# LINEARDriver_Driver.net
KiCad netlist of a schematic drawn in Altium Designer
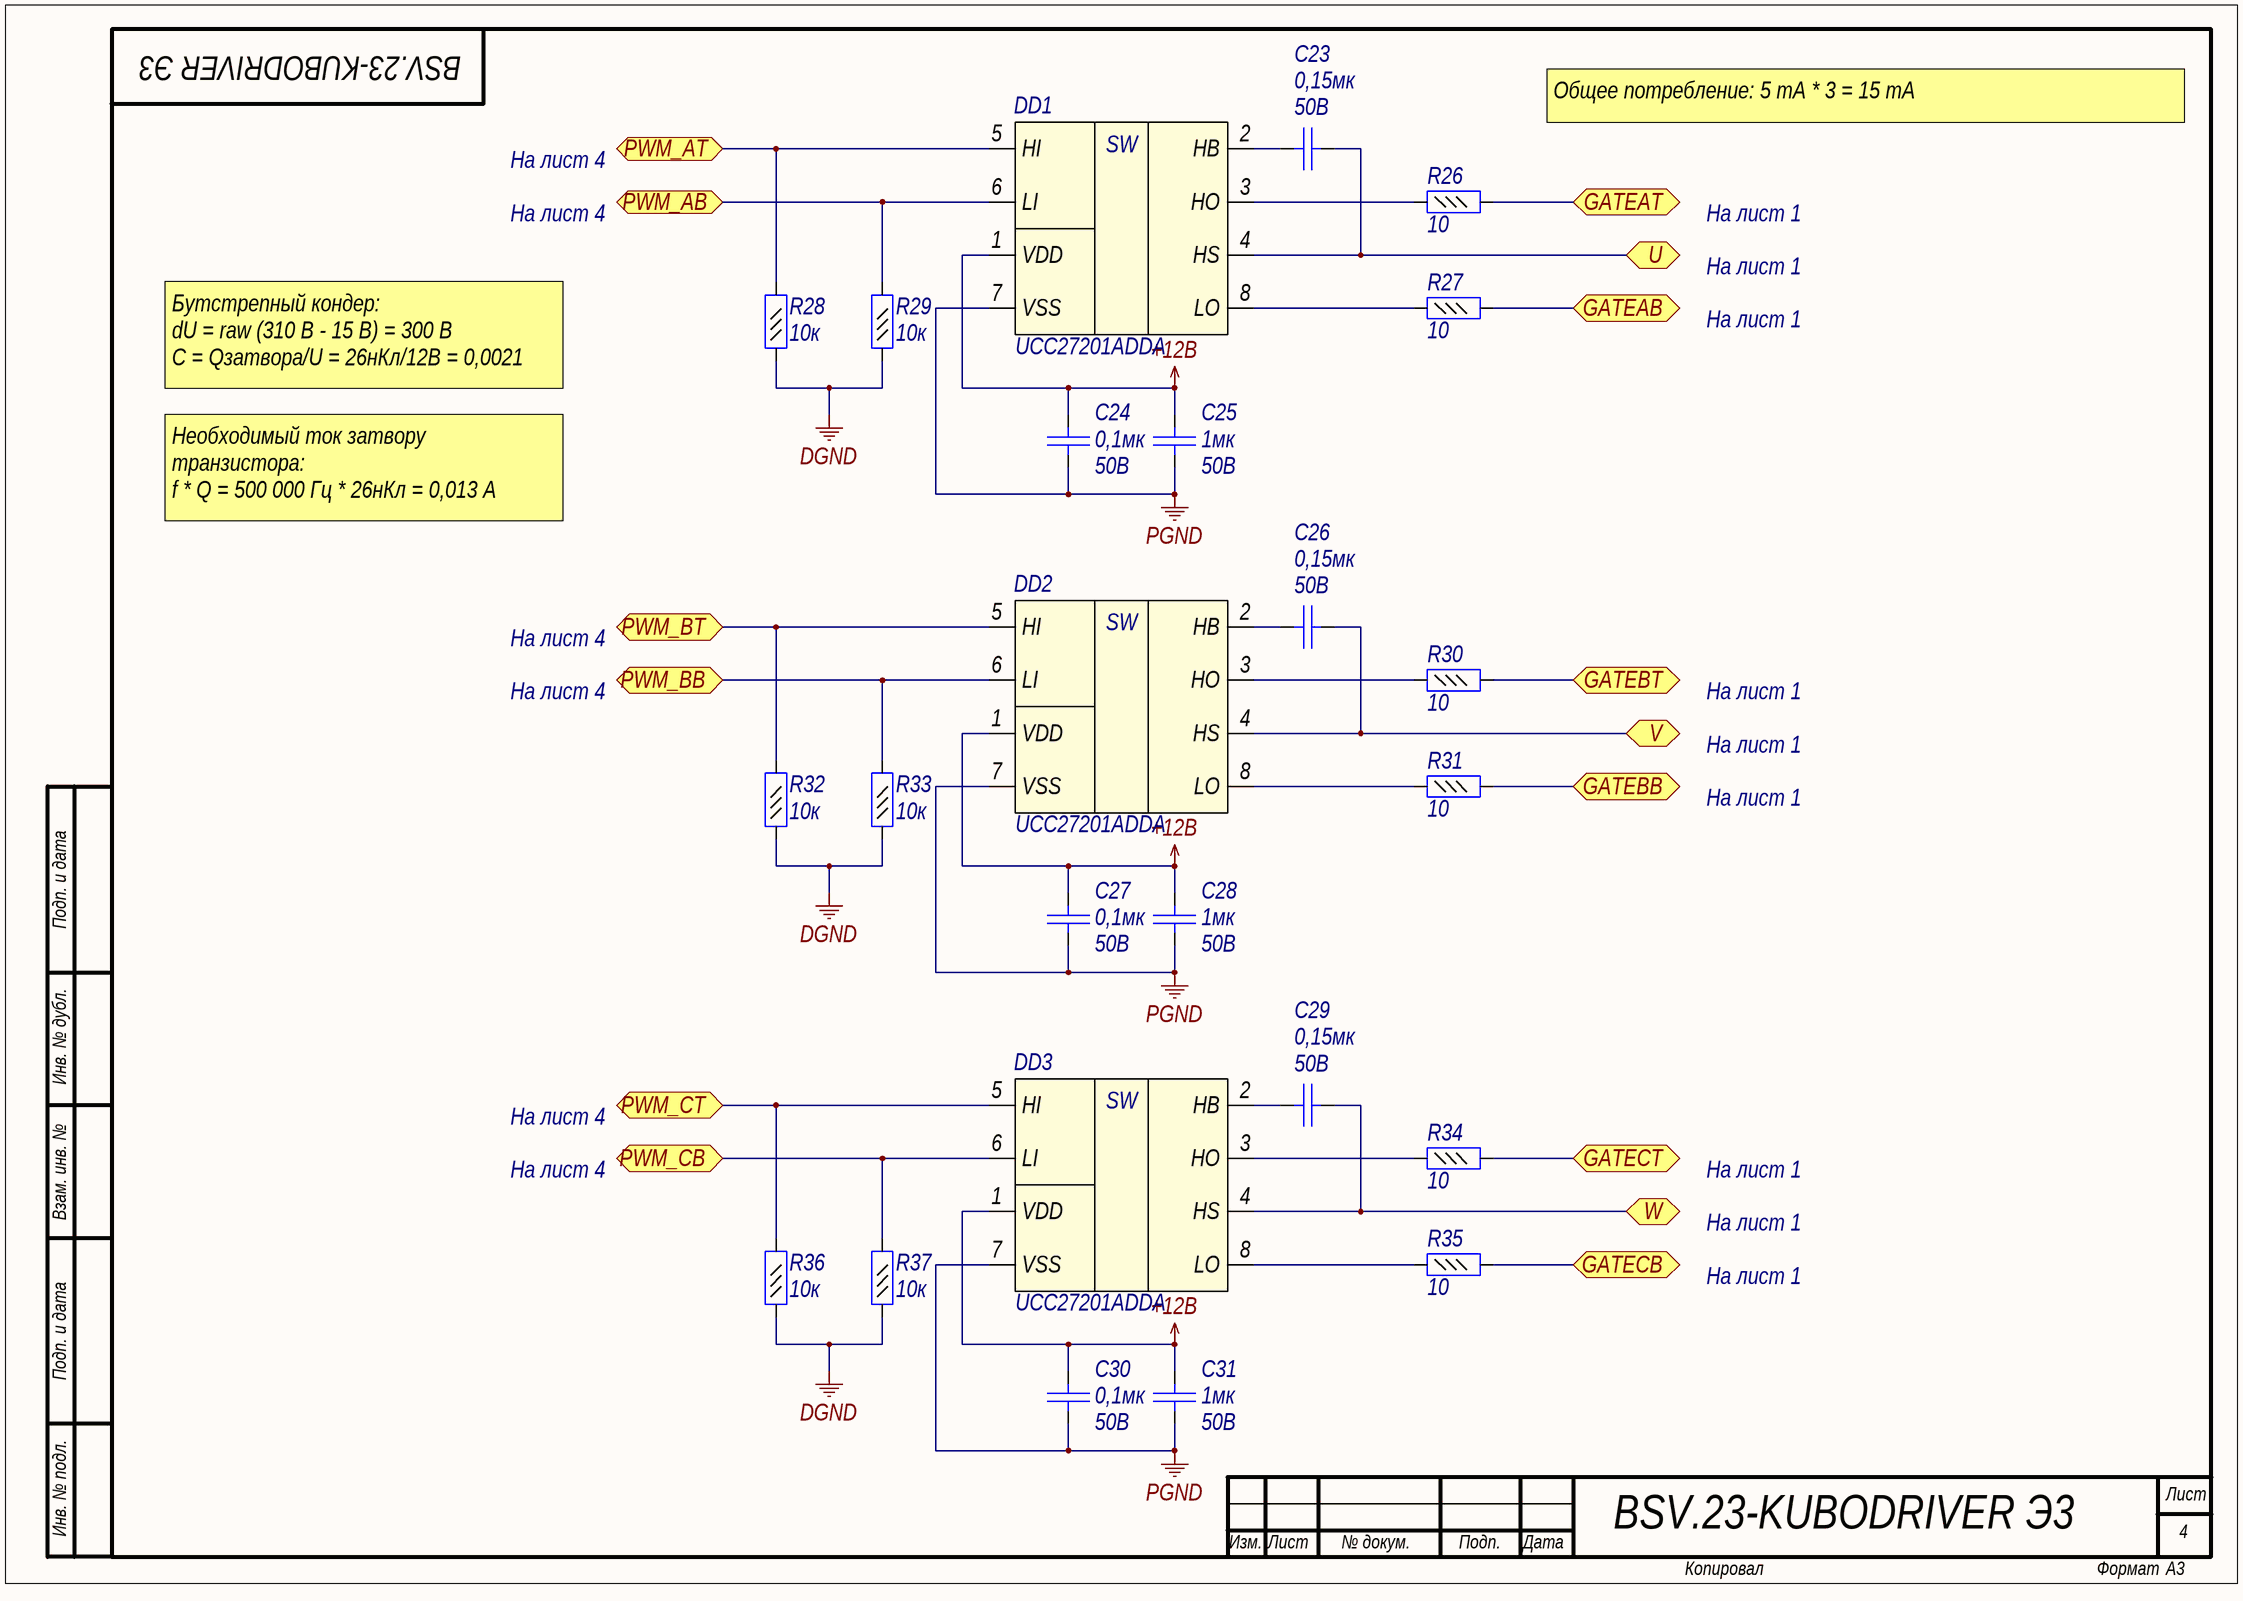
[diagram p0: LINEARDriver_Driver.SchDoc]

(export (version "E")
  (design (tool "Eeschema 10.0.6"))
  (components
    (comp (ref "C23")
      (value "0,15мк")
      (footprint "C1812")
      (description "Конденсатор")
      (fields (field (name "VOLTAGE") "50В") (field (name "PART NUMBER") "C4532C0G1H154J250KA "))
      (libsource (lib "MOP44") (part "Capacitor"))
    )
    (comp (ref "C24")
      (value "0,1мк")
      (footprint "C0402")
      (description "Конденсатор")
      (fields
        (field (name "VOLTAGE") "50В")
        (field (name "PART NUMBER") "GRM155R71H104KE14D ")
        (field (name "Comment") "Capacitor")
      )
      (libsource (lib "MOP44") (part "Capacitor"))
    )
    (comp (ref "C25")
      (value "1мк")
      (footprint "C0805")
      (description "Конденсатор")
      (fields
        (field (name "VOLTAGE") "50B")
        (field (name "PART NUMBER") "GRM21BR71H105K")
        (field (name "Comment") "Capacitor")
      )
      (libsource (lib "MOP44") (part "Capacitor"))
    )
    (comp (ref "C26")
      (value "0,15мк")
      (footprint "C1812")
      (description "Конденсатор")
      (fields (field (name "VOLTAGE") "50В") (field (name "PART NUMBER") "C4532C0G1H154J250KA "))
      (libsource (lib "MOP44") (part "Capacitor"))
    )
    (comp (ref "C27")
      (value "0,1мк")
      (footprint "C0402")
      (description "Конденсатор")
      (fields
        (field (name "VOLTAGE") "50В")
        (field (name "PART NUMBER") "GRM155R71H104KE14D ")
        (field (name "Comment") "Capacitor")
      )
      (libsource (lib "MOP44") (part "Capacitor"))
    )
    (comp (ref "C28")
      (value "1мк")
      (footprint "C0805")
      (description "Конденсатор")
      (fields
        (field (name "VOLTAGE") "50B")
        (field (name "PART NUMBER") "GRM21BR71H105K")
        (field (name "Comment") "Capacitor")
      )
      (libsource (lib "MOP44") (part "Capacitor"))
    )
    (comp (ref "C29")
      (value "0,15мк")
      (footprint "C1812")
      (description "Конденсатор")
      (fields (field (name "VOLTAGE") "50В") (field (name "PART NUMBER") "C4532C0G1H154J250KA "))
      (libsource (lib "MOP44") (part "Capacitor"))
    )
    (comp (ref "C30")
      (value "0,1мк")
      (footprint "C0402")
      (description "Конденсатор")
      (fields
        (field (name "VOLTAGE") "50В")
        (field (name "PART NUMBER") "GRM155R71H104KE14D ")
        (field (name "Comment") "Capacitor")
      )
      (libsource (lib "MOP44") (part "Capacitor"))
    )
    (comp (ref "C31")
      (value "1мк")
      (footprint "C0805")
      (description "Конденсатор")
      (fields
        (field (name "VOLTAGE") "50B")
        (field (name "PART NUMBER") "GRM21BR71H105K")
        (field (name "Comment") "Capacitor")
      )
      (libsource (lib "MOP44") (part "Capacitor"))
    )
    (comp (ref "DD1")
      (value "UCC27201A")
      (footprint "HSOP8")
      (description "120-V Boot, 3-A Peak, High-Frequency, High-Side and Low-Side Driver")
      (fields (field (name "PART NUMBER") "UCC27201ADDA"))
      (libsource (lib "MOP44") (part "UCC27201A"))
    )
    (comp (ref "DD2")
      (value "UCC27201A")
      (footprint "HSOP8")
      (description "120-V Boot, 3-A Peak, High-Frequency, High-Side and Low-Side Driver")
      (fields (field (name "PART NUMBER") "UCC27201ADDA"))
      (libsource (lib "MOP44") (part "UCC27201A"))
    )
    (comp (ref "DD3")
      (value "UCC27201A")
      (footprint "HSOP8")
      (description "120-V Boot, 3-A Peak, High-Frequency, High-Side and Low-Side Driver")
      (fields (field (name "PART NUMBER") "UCC27201ADDA"))
      (libsource (lib "MOP44") (part "UCC27201A"))
    )
    (comp (ref "R26")
      (value "10")
      (footprint "R0402")
      (description "Резистор")
      (fields (field (name "PART NUMBER") "RC0402FR-0710RL") (field (name "POWER") "0,062Вт"))
      (libsource (lib "") (part "Resistor_0,062Вт_1"))
    )
    (comp (ref "R27")
      (value "10")
      (footprint "R0402")
      (description "Резистор")
      (fields (field (name "PART NUMBER") "RC0402FR-0710RL") (field (name "POWER") "0,062Вт"))
      (libsource (lib "") (part "Resistor_0,062Вт_1"))
    )
    (comp (ref "R28")
      (value "10к")
      (footprint "R0402")
      (description "Резистор")
      (fields (field (name "PART NUMBER") "RC0402FR-0710KL") (field (name "POWER") "0,062Вт"))
      (libsource (lib "MOP44") (part "Resistor_0,062Вт"))
    )
    (comp (ref "R29")
      (value "10к")
      (footprint "R0402")
      (description "Резистор")
      (fields (field (name "PART NUMBER") "RC0402FR-0710KL") (field (name "POWER") "0,062Вт"))
      (libsource (lib "MOP44") (part "Resistor_0,062Вт"))
    )
    (comp (ref "R30")
      (value "10")
      (footprint "R0402")
      (description "Резистор")
      (fields (field (name "PART NUMBER") "RC0402FR-0710RL") (field (name "POWER") "0,062Вт"))
      (libsource (lib "") (part "Resistor_0,062Вт_1"))
    )
    (comp (ref "R31")
      (value "10")
      (footprint "R0402")
      (description "Резистор")
      (fields (field (name "PART NUMBER") "RC0402FR-0710RL") (field (name "POWER") "0,062Вт"))
      (libsource (lib "") (part "Resistor_0,062Вт_1"))
    )
    (comp (ref "R32")
      (value "10к")
      (footprint "R0402")
      (description "Резистор")
      (fields (field (name "PART NUMBER") "RC0402FR-0710KL") (field (name "POWER") "0,062Вт"))
      (libsource (lib "MOP44") (part "Resistor_0,062Вт"))
    )
    (comp (ref "R33")
      (value "10к")
      (footprint "R0402")
      (description "Резистор")
      (fields (field (name "PART NUMBER") "RC0402FR-0710KL") (field (name "POWER") "0,062Вт"))
      (libsource (lib "MOP44") (part "Resistor_0,062Вт"))
    )
    (comp (ref "R34")
      (value "10")
      (footprint "R0402")
      (description "Резистор")
      (fields (field (name "PART NUMBER") "RC0402FR-0710RL") (field (name "POWER") "0,062Вт"))
      (libsource (lib "") (part "Resistor_0,062Вт_1"))
    )
    (comp (ref "R35")
      (value "10")
      (footprint "R0402")
      (description "Резистор")
      (fields (field (name "PART NUMBER") "RC0402FR-0710RL") (field (name "POWER") "0,062Вт"))
      (libsource (lib "") (part "Resistor_0,062Вт_1"))
    )
    (comp (ref "R36")
      (value "10к")
      (footprint "R0402")
      (description "Резистор")
      (fields (field (name "PART NUMBER") "RC0402FR-0710KL") (field (name "POWER") "0,062Вт"))
      (libsource (lib "MOP44") (part "Resistor_0,062Вт"))
    )
    (comp (ref "R37")
      (value "10к")
      (footprint "R0402")
      (description "Резистор")
      (fields (field (name "PART NUMBER") "RC0402FR-0710KL") (field (name "POWER") "0,062Вт"))
      (libsource (lib "MOP44") (part "Resistor_0,062Вт"))
    )
  )
  (nets
    (net (code "1") (name "+12B") (class "Default")
      (node (ref "C24") (pin "2") (pinfunction "2_2") (pintype "passive"))
      (node (ref "C25") (pin "2") (pinfunction "2_2") (pintype "passive"))
      (node (ref "C27") (pin "2") (pinfunction "2_2") (pintype "passive"))
      (node (ref "C28") (pin "2") (pinfunction "2_2") (pintype "passive"))
      (node (ref "C30") (pin "2") (pinfunction "2_2") (pintype "passive"))
      (node (ref "C31") (pin "2") (pinfunction "2_2") (pintype "passive"))
      (node (ref "DD1") (pin "1") (pinfunction "VDD_1") (pintype "passive"))
      (node (ref "DD2") (pin "1") (pinfunction "VDD_1") (pintype "passive"))
      (node (ref "DD3") (pin "1") (pinfunction "VDD_1") (pintype "passive"))
    )
    (net (code "2") (name "/GATEAB") (class "Default")
      (node (ref "R27") (pin "2") (pinfunction "2_2") (pintype "passive"))
    )
    (net (code "3") (name "/GATEAT") (class "Default")
      (node (ref "R26") (pin "2") (pinfunction "2_2") (pintype "passive"))
    )
    (net (code "4") (name "/GATEBB") (class "Default")
      (node (ref "R31") (pin "2") (pinfunction "2_2") (pintype "passive"))
    )
    (net (code "5") (name "/GATEBT") (class "Default")
      (node (ref "R30") (pin "2") (pinfunction "2_2") (pintype "passive"))
    )
    (net (code "6") (name "/GATECB") (class "Default")
      (node (ref "R35") (pin "2") (pinfunction "2_2") (pintype "passive"))
    )
    (net (code "7") (name "/GATECT") (class "Default")
      (node (ref "R34") (pin "2") (pinfunction "2_2") (pintype "passive"))
    )
    (net (code "8") (name "/PWM_AB") (class "Default")
      (node (ref "DD1") (pin "6") (pinfunction "LI_6") (pintype "passive"))
      (node (ref "R29") (pin "2") (pinfunction "2_2") (pintype "passive"))
    )
    (net (code "9") (name "/PWM_AT") (class "Default")
      (node (ref "DD1") (pin "5") (pinfunction "HI_5") (pintype "passive"))
      (node (ref "R28") (pin "2") (pinfunction "2_2") (pintype "passive"))
    )
    (net (code "10") (name "/PWM_BB") (class "Default")
      (node (ref "DD2") (pin "6") (pinfunction "LI_6") (pintype "passive"))
      (node (ref "R33") (pin "2") (pinfunction "2_2") (pintype "passive"))
    )
    (net (code "11") (name "/PWM_BT") (class "Default")
      (node (ref "DD2") (pin "5") (pinfunction "HI_5") (pintype "passive"))
      (node (ref "R32") (pin "2") (pinfunction "2_2") (pintype "passive"))
    )
    (net (code "12") (name "/PWM_CB") (class "Default")
      (node (ref "DD3") (pin "6") (pinfunction "LI_6") (pintype "passive"))
      (node (ref "R37") (pin "2") (pinfunction "2_2") (pintype "passive"))
    )
    (net (code "13") (name "/PWM_CT") (class "Default")
      (node (ref "DD3") (pin "5") (pinfunction "HI_5") (pintype "passive"))
      (node (ref "R36") (pin "2") (pinfunction "2_2") (pintype "passive"))
    )
    (net (code "14") (name "/U") (class "Default")
      (node (ref "C23") (pin "2") (pinfunction "2_2") (pintype "passive"))
      (node (ref "DD1") (pin "4") (pinfunction "HS_4") (pintype "passive"))
    )
    (net (code "15") (name "/V") (class "Default")
      (node (ref "C26") (pin "2") (pinfunction "2_2") (pintype "passive"))
      (node (ref "DD2") (pin "4") (pinfunction "HS_4") (pintype "passive"))
    )
    (net (code "16") (name "/W") (class "Default")
      (node (ref "C29") (pin "2") (pinfunction "2_2") (pintype "passive"))
      (node (ref "DD3") (pin "4") (pinfunction "HS_4") (pintype "passive"))
    )
    (net (code "17") (name "DGND") (class "Default")
      (node (ref "R28") (pin "1") (pinfunction "1_1") (pintype "passive"))
      (node (ref "R29") (pin "1") (pinfunction "1_1") (pintype "passive"))
      (node (ref "R32") (pin "1") (pinfunction "1_1") (pintype "passive"))
      (node (ref "R33") (pin "1") (pinfunction "1_1") (pintype "passive"))
      (node (ref "R36") (pin "1") (pinfunction "1_1") (pintype "passive"))
      (node (ref "R37") (pin "1") (pinfunction "1_1") (pintype "passive"))
    )
    (net (code "18") (name "Net-(DD1-HB)") (class "Default")
      (node (ref "C23") (pin "1") (pinfunction "1_1") (pintype "passive"))
      (node (ref "DD1") (pin "2") (pinfunction "HB_2") (pintype "passive"))
    )
    (net (code "19") (name "Net-(DD1-HO)") (class "Default")
      (node (ref "DD1") (pin "3") (pinfunction "HO_3") (pintype "passive"))
      (node (ref "R26") (pin "1") (pinfunction "1_1") (pintype "passive"))
    )
    (net (code "20") (name "Net-(DD1-LO)") (class "Default")
      (node (ref "DD1") (pin "8") (pinfunction "LO_8") (pintype "passive"))
      (node (ref "R27") (pin "1") (pinfunction "1_1") (pintype "passive"))
    )
    (net (code "21") (name "Net-(DD2-HB)") (class "Default")
      (node (ref "C26") (pin "1") (pinfunction "1_1") (pintype "passive"))
      (node (ref "DD2") (pin "2") (pinfunction "HB_2") (pintype "passive"))
    )
    (net (code "22") (name "Net-(DD2-HO)") (class "Default")
      (node (ref "DD2") (pin "3") (pinfunction "HO_3") (pintype "passive"))
      (node (ref "R30") (pin "1") (pinfunction "1_1") (pintype "passive"))
    )
    (net (code "23") (name "Net-(DD2-LO)") (class "Default")
      (node (ref "DD2") (pin "8") (pinfunction "LO_8") (pintype "passive"))
      (node (ref "R31") (pin "1") (pinfunction "1_1") (pintype "passive"))
    )
    (net (code "24") (name "Net-(DD3-HB)") (class "Default")
      (node (ref "C29") (pin "1") (pinfunction "1_1") (pintype "passive"))
      (node (ref "DD3") (pin "2") (pinfunction "HB_2") (pintype "passive"))
    )
    (net (code "25") (name "Net-(DD3-HO)") (class "Default")
      (node (ref "DD3") (pin "3") (pinfunction "HO_3") (pintype "passive"))
      (node (ref "R34") (pin "1") (pinfunction "1_1") (pintype "passive"))
    )
    (net (code "26") (name "Net-(DD3-LO)") (class "Default")
      (node (ref "DD3") (pin "8") (pinfunction "LO_8") (pintype "passive"))
      (node (ref "R35") (pin "1") (pinfunction "1_1") (pintype "passive"))
    )
    (net (code "27") (name "PGND") (class "Default")
      (node (ref "C24") (pin "1") (pinfunction "1_1") (pintype "passive"))
      (node (ref "C25") (pin "1") (pinfunction "1_1") (pintype "passive"))
      (node (ref "C27") (pin "1") (pinfunction "1_1") (pintype "passive"))
      (node (ref "C28") (pin "1") (pinfunction "1_1") (pintype "passive"))
      (node (ref "C30") (pin "1") (pinfunction "1_1") (pintype "passive"))
      (node (ref "C31") (pin "1") (pinfunction "1_1") (pintype "passive"))
      (node (ref "DD1") (pin "7") (pinfunction "VSS_7") (pintype "passive"))
      (node (ref "DD2") (pin "7") (pinfunction "VSS_7") (pintype "passive"))
      (node (ref "DD3") (pin "7") (pinfunction "VSS_7") (pintype "passive"))
    )
  )
)
